# EduBOT_v2.net
KiCad netlist of a schematic drawn in Altium Designer
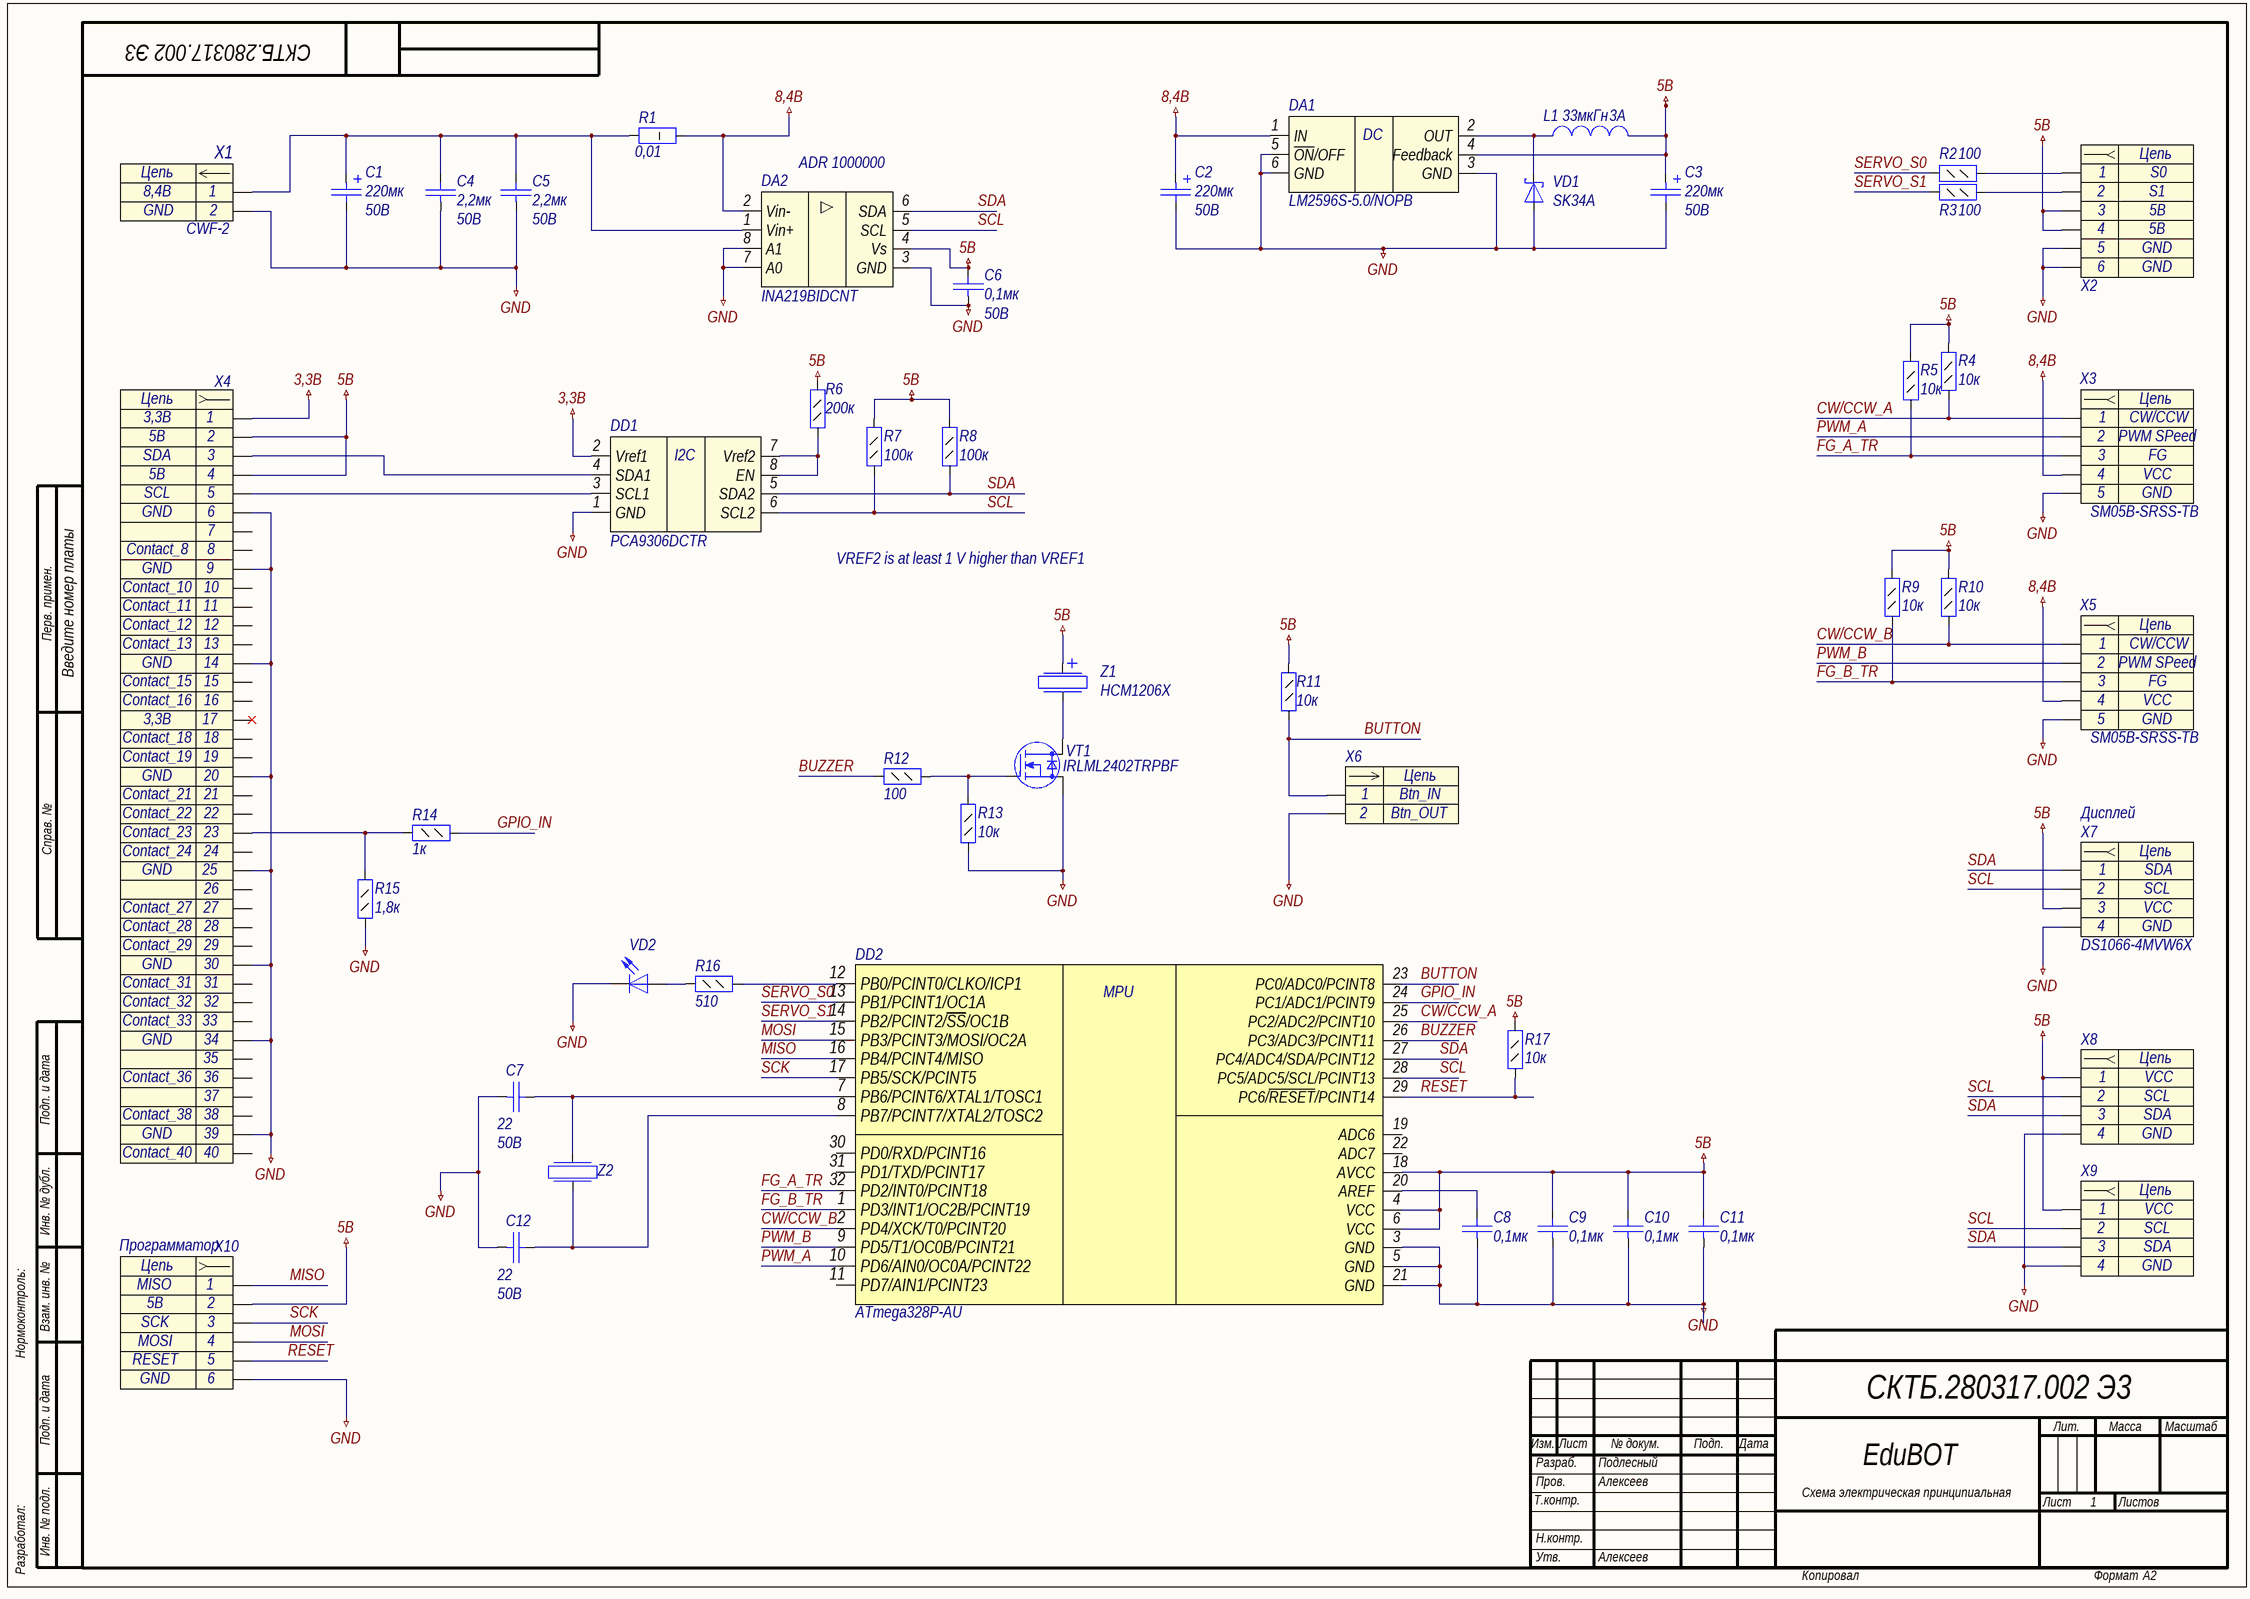
[diagram p0: EduBOT_v2.SchDoc]

(export (version "E")
  (design (tool "Eeschema 10.0.6"))
  (components
    (comp (ref "C1")
      (value "220мк")
      (footprint "Cap_SMD_radial_polar(10x10.5)")
      (description "Конденсатор полярный")
      (fields
        (field (name "VOLTAGE") "50В")
        (field (name "PART NUMBER") "ECAP SMD")
        (field (name "Comment") "Capacitor_pol")
      )
      (libsource (lib "MOP44") (part "Capacitor_pol"))
    )
    (comp (ref "C2")
      (value "220мк")
      (footprint "Cap_SMD_radial_polar(10x10.5)")
      (description "Конденсатор полярный")
      (fields
        (field (name "VOLTAGE") "50В")
        (field (name "PART NUMBER") "ECAP SMD")
        (field (name "Comment") "Capacitor_pol")
      )
      (libsource (lib "MOP44") (part "Capacitor_pol"))
    )
    (comp (ref "C3")
      (value "220мк")
      (footprint "Cap_SMD_radial_polar(10x10.5)")
      (description "Конденсатор полярный")
      (fields
        (field (name "VOLTAGE") "50В")
        (field (name "PART NUMBER") "ECAP SMD")
        (field (name "Comment") "Capacitor_pol")
      )
      (libsource (lib "MOP44") (part "Capacitor_pol"))
    )
    (comp (ref "C4")
      (value "2,2мк")
      (footprint "C1206")
      (description "Конденсатор")
      (fields
        (field (name "VOLTAGE") "50В")
        (field (name "PART NUMBER") "GRM31CR71H225KA88**L")
        (field (name "Comment") "Capacitor")
      )
      (libsource (lib "MOP44") (part "Capacitor"))
    )
    (comp (ref "C5")
      (value "2,2мк")
      (footprint "C1206")
      (description "Конденсатор")
      (fields
        (field (name "VOLTAGE") "50В")
        (field (name "PART NUMBER") "GRM31CR71H225KA88**L")
        (field (name "Comment") "Capacitor")
      )
      (libsource (lib "MOP44") (part "Capacitor"))
    )
    (comp (ref "C6")
      (value "0,1мк")
      (footprint "C0805")
      (description "Конденсатор")
      (fields
        (field (name "VOLTAGE") "50В")
        (field (name "PART NUMBER") "GRM21BR71H104KA01L ")
        (field (name "Comment") "Capacitor")
      )
      (libsource (lib "MOP44") (part "Capacitor"))
    )
    (comp (ref "C7")
      (value "22")
      (footprint "C0805")
      (description "Конденсатор")
      (fields
        (field (name "VOLTAGE") "50В")
        (field (name "PART NUMBER") "GRM21A5C2E220JW01D")
        (field (name "Comment") "Capacitor")
      )
      (libsource (lib "MOP44") (part "Capacitor"))
    )
    (comp (ref "C8")
      (value "0,1мк")
      (footprint "C0805")
      (description "Конденсатор")
      (fields (field (name "PART NUMBER") "GRM21BR71H104KA01L ") (field (name "Comment") "Capacitor"))
      (libsource (lib "MOP44") (part "Capacitor"))
    )
    (comp (ref "C9")
      (value "0,1мк")
      (footprint "C0805")
      (description "Конденсатор")
      (fields (field (name "PART NUMBER") "GRM21BR71H104KA01L ") (field (name "Comment") "Capacitor"))
      (libsource (lib "MOP44") (part "Capacitor"))
    )
    (comp (ref "C10")
      (value "0,1мк")
      (footprint "C0805")
      (description "Конденсатор")
      (fields (field (name "PART NUMBER") "GRM21BR71H104KA01L ") (field (name "Comment") "Capacitor"))
      (libsource (lib "MOP44") (part "Capacitor"))
    )
    (comp (ref "C11")
      (value "0,1мк")
      (footprint "C0805")
      (description "Конденсатор")
      (fields (field (name "PART NUMBER") "GRM21BR71H104KA01L ") (field (name "Comment") "Capacitor"))
      (libsource (lib "MOP44") (part "Capacitor"))
    )
    (comp (ref "C12")
      (value "22")
      (footprint "C0805")
      (description "Конденсатор")
      (fields
        (field (name "VOLTAGE") "50В")
        (field (name "PART NUMBER") "GRM21A5C2E220JW01D")
        (field (name "Comment") "Capacitor")
      )
      (libsource (lib "MOP44") (part "Capacitor"))
    )
    (comp (ref "DA1")
      (value "LM2596S")
      (footprint "TO-263-5")
      (description "3-A Step-Down Voltage Regulator")
      (fields
        (field (name "PART NUMBER") "LM2596S-5.0/NOPB")
        (field (name "MANUFACTURER") "Texas Instruments")
      )
      (libsource (lib "MOP44") (part "LM2596S"))
    )
    (comp (ref "DA2")
      (value "INA219BIDCNT")
      (footprint "SOT23-8")
      (description "Токочувствительный усилитель")
      (libsource (lib "MOP44") (part "INA219BIDCNT"))
    )
    (comp (ref "DD1")
      (value "PCA9306DCTR")
      (footprint "SSOP8")
      (description "DUAL BIDIRECTIONAL I2C BUS AND SMBus VOLTAGE-LEVEL TRANSLATOR")
      (libsource (lib "MOP44") (part "PCA9306DCTR"))
    )
    (comp (ref "DD2")
      (value "ATmega328P-AU")
      (footprint "TQFP-32")
      (description "Микроконтроллер 8-Бит, picoPower, AVR, 20МГц, 32КБ Flash")
      (fields (field (name "PART NUMBER") "ATmega328P-AU"))
      (libsource (lib "MOP44") (part "ATmega328P-AU"))
    )
    (comp (ref "L1")
      (value "33мкГн")
      (footprint "IND_12.8x12.8")
      (description "EMI Suppression Filter")
      (fields
        (field (name "RATED CURRENT") "3A")
        (field (name "PART NUMBER") "B82477G4333M000")
        (field (name "Comment") "Inductor")
      )
      (libsource (lib "MOP44") (part "Inductor"))
    )
    (comp (ref "R1")
      (value "0,01")
      (footprint "R2512")
      (description "Резистор")
      (fields (field (name "PART NUMBER") "RL2512FK-070R01L") (field (name "POWER") "1Вт"))
      (libsource (lib "MOP44") (part "Resistor_1Вт"))
    )
    (comp (ref "R2")
      (value "100")
      (footprint "R0805")
      (description "Резистор")
      (fields (field (name "PART NUMBER") "RC0805FR-07100RL") (field (name "POWER") "0,125Вт"))
      (libsource (lib "") (part "Resistor_0,125Вт_3"))
    )
    (comp (ref "R3")
      (value "100")
      (footprint "R0805")
      (description "Резистор")
      (fields (field (name "PART NUMBER") "RC0805FR-07100RL") (field (name "POWER") "0,125Вт"))
      (libsource (lib "") (part "Resistor_0,125Вт_3"))
    )
    (comp (ref "R4")
      (value "10к")
      (footprint "R0805")
      (description "Резистор")
      (fields (field (name "PART NUMBER") "RC0805FR-0710KL") (field (name "POWER") "0,125Вт"))
      (libsource (lib "MOP44") (part "Resistor_0,125Вт"))
    )
    (comp (ref "R5")
      (value "10к")
      (footprint "R0805")
      (description "Резистор")
      (fields (field (name "PART NUMBER") "RC0805FR-0710KL") (field (name "POWER") "0,125Вт"))
      (libsource (lib "MOP44") (part "Resistor_0,125Вт"))
    )
    (comp (ref "R6")
      (value "200к")
      (footprint "R0805")
      (description "Резистор")
      (fields (field (name "PART NUMBER") "RC0805FR-07200KL") (field (name "POWER") "0,125Вт"))
      (libsource (lib "MOP44") (part "Resistor_0,125Вт"))
    )
    (comp (ref "R7")
      (value "100к")
      (footprint "R0805")
      (description "Резистор")
      (fields (field (name "PART NUMBER") "RC0805FR-07100KL") (field (name "POWER") "0,125Вт"))
      (libsource (lib "MOP44") (part "Resistor_0,125Вт"))
    )
    (comp (ref "R8")
      (value "100к")
      (footprint "R0805")
      (description "Резистор")
      (fields (field (name "PART NUMBER") "RC0805FR-07100KL") (field (name "POWER") "0,125Вт"))
      (libsource (lib "MOP44") (part "Resistor_0,125Вт"))
    )
    (comp (ref "R9")
      (value "10к")
      (footprint "R0805")
      (description "Резистор")
      (fields (field (name "PART NUMBER") "RC0805FR-0710KL") (field (name "POWER") "0,125Вт"))
      (libsource (lib "MOP44") (part "Resistor_0,125Вт"))
    )
    (comp (ref "R10")
      (value "10к")
      (footprint "R0805")
      (description "Резистор")
      (fields (field (name "PART NUMBER") "RC0805FR-0710KL") (field (name "POWER") "0,125Вт"))
      (libsource (lib "MOP44") (part "Resistor_0,125Вт"))
    )
    (comp (ref "R11")
      (value "10к")
      (footprint "R0805")
      (description "Резистор")
      (fields (field (name "POWER") "0,125Вт") (field (name "Comment") "Resistor_0,125Вт"))
      (libsource (lib "") (part "Resistor_0,125Вт_2"))
    )
    (comp (ref "R12")
      (value "100")
      (footprint "R0805")
      (description "Резистор")
      (fields (field (name "PART NUMBER") "RC0805FR-07100RL") (field (name "POWER") "0,125Вт"))
      (libsource (lib "") (part "Resistor_0,125Вт_3"))
    )
    (comp (ref "R13")
      (value "10к")
      (footprint "R0805")
      (description "Резистор")
      (fields (field (name "PART NUMBER") "RC0805FR-0710KL") (field (name "POWER") "0,125Вт"))
      (libsource (lib "MOP44") (part "Resistor_0,125Вт"))
    )
    (comp (ref "R14")
      (value "1к")
      (footprint "R0805")
      (description "Резистор")
      (fields (field (name "PART NUMBER") "RC0805FR-071KL") (field (name "POWER") "0,125Вт"))
      (libsource (lib "") (part "Resistor_0,125Вт_1"))
    )
    (comp (ref "R15")
      (value "1,8к")
      (footprint "R0805")
      (description "Резистор")
      (fields (field (name "PART NUMBER") "RC0805FR-071K8") (field (name "POWER") "0,125Вт"))
      (libsource (lib "MOP44") (part "Resistor_0,125Вт"))
    )
    (comp (ref "R16")
      (value "510")
      (footprint "R0805")
      (description "Резистор")
      (fields (field (name "PART NUMBER") "RC0805FR-07510RL") (field (name "POWER") "0,125Вт"))
      (libsource (lib "") (part "Resistor_0,125Вт_3"))
    )
    (comp (ref "R17")
      (value "10к")
      (footprint "R0805")
      (description "Резистор")
      (fields (field (name "PART NUMBER") "RC0805FR-0710KL") (field (name "POWER") "0,125Вт"))
      (libsource (lib "MOP44") (part "Resistor_0,125Вт"))
    )
    (comp (ref "VD1")
      (value "DiodeSchottky")
      (footprint "SMA")
      (description "Диод Шоттки")
      (fields (field (name "PART NUMBER") "SK34A"))
      (libsource (lib "MOP44") (part "DiodeSchottky"))
    )
    (comp (ref "VD2")
      (value "LED")
      (footprint "L_0805")
      (description "Светодиод")
      (fields (field (name "PART NUMBER") "KP-2012EC"))
      (libsource (lib "MOP44") (part "LED"))
    )
    (comp (ref "VT1")
      (value "N-MOSFET")
      (footprint "SOT23-3")
      (fields
        (field (name "PART NUMBER") "IRLML2402TRPBF")
        (field (name "MANUFACTURER") "International Rectifier")
      )
      (libsource (lib "MOP44") (part "N-MOSFET"))
    )
    (comp (ref "X1")
      (value "~")
      (footprint "CWF-2")
      (description "Разъем - 2 конт. вилка")
      (fields (field (name "PART NAME") "CWF-2") (field (name "PART NUMBER") "DS1069-2MVW6X"))
      (libsource (lib "MOP44") (part "Header_2_plg"))
    )
    (comp (ref "X2")
      (value "Header_6_sct")
      (footprint "PLS2-6")
      (description "Разъем - 6 конт. розетка")
      (libsource (lib "MOP44") (part "Header_6_sct"))
    )
    (comp (ref "X3")
      (value "Двигатель А")
      (footprint "SM05B-SRSS-TB")
      (description "Разъем - 5 конт. розетка")
      (fields (field (name "PART NUMBER") "SM05B-SRSS-TB"))
      (libsource (lib "MOP44") (part "Header_5_sct"))
    )
    (comp (ref "X4")
      (value "~")
      (footprint "ZabugorLib:PBS-40")
      (description "Разъем - 5 конт. розетка")
      (libsource (lib "ZabugorLib") (part "Header_40"))
    )
    (comp (ref "X5")
      (value "Двигатель А")
      (footprint "SM05B-SRSS-TB")
      (description "Разъем - 5 конт. розетка")
      (fields (field (name "PART NUMBER") "SM05B-SRSS-TB"))
      (libsource (lib "MOP44") (part "Header_5_sct"))
    )
    (comp (ref "X6")
      (value "~")
      (footprint "JUMPER_2.54")
      (description "Разъем - 2 конт. вилка")
      (libsource (lib "") (part "Header_2_plg_1"))
    )
    (comp (ref "X7")
      (value "Дисплей")
      (footprint "MW-4M")
      (description "Разъем - 4 конт. розетка")
      (fields (field (name "PART NUMBER") "DS1066-4MVW6X"))
      (libsource (lib "MOP44") (part "Header_4_sct"))
    )
    (comp (ref "X8")
      (value "Header_4_sct")
      (footprint "RJ9_4P4C")
      (description "Разъем - 4 конт. розетка")
      (libsource (lib "MOP44") (part "Header_4_sct"))
    )
    (comp (ref "X9")
      (value "Header_4_sct")
      (footprint "RJ9_4P4C")
      (description "Разъем - 4 конт. розетка")
      (libsource (lib "MOP44") (part "Header_4_sct"))
    )
    (comp (ref "X10")
      (value "Программатор")
      (footprint "PLS2-6")
      (description "Разъем - 6 конт. розетка")
      (libsource (lib "") (part "Header_6_sct_1"))
    )
    (comp (ref "Z1")
      (value "~")
      (footprint "Buzzer_gen_12mm")
      (description "Пьезоизлучатель звуковой без генератора")
      (fields (field (name "PART NUMBER") "HCM1206X"))
      (libsource (lib "MOP44") (part "Buzzer"))
    )
    (comp (ref "Z2")
      (value "Crystal")
      (footprint "HC-49S")
      (description "Кварцевый резонатор")
      (fields (field (name "PART NUMBER") "16.000MHzHC-49US"))
      (libsource (lib "MOP44") (part "Crystal"))
    )
  )
  (nets
    (net (code "1") (name "/BUTTON") (class "Default")
      (node (ref "DD2") (pin "23") (pinfunction "PC0/ADC0/PCINT8_23") (pintype "passive"))
      (node (ref "R11") (pin "2") (pinfunction "2_2") (pintype "passive"))
      (node (ref "X6") (pin "1") (pinfunction "1_1") (pintype "passive"))
    )
    (net (code "2") (name "/BUZZER") (class "Default")
      (node (ref "DD2") (pin "26") (pinfunction "PC3/ADC3/PCINT11_26") (pintype "passive"))
      (node (ref "R12") (pin "1") (pinfunction "1_1") (pintype "passive"))
    )
    (net (code "3") (name "/CW{slash}CCW_A") (class "Default")
      (node (ref "DD2") (pin "25") (pinfunction "PC2/ADC2/PCINT10_25") (pintype "passive"))
      (node (ref "R4") (pin "1") (pinfunction "1_1") (pintype "passive"))
      (node (ref "X3") (pin "1") (pinfunction "1_1") (pintype "passive"))
    )
    (net (code "4") (name "/CW{slash}CCW_B") (class "Default")
      (node (ref "DD2") (pin "2") (pinfunction "PD4/XCK/T0/PCINT20_2") (pintype "passive"))
      (node (ref "R10") (pin "1") (pinfunction "1_1") (pintype "passive"))
      (node (ref "X5") (pin "1") (pinfunction "1_1") (pintype "passive"))
    )
    (net (code "5") (name "/FG_A_TR") (class "Default")
      (node (ref "DD2") (pin "32") (pinfunction "PD2/INT0/PCINT18_32") (pintype "passive"))
      (node (ref "R5") (pin "1") (pinfunction "1_1") (pintype "passive"))
      (node (ref "X3") (pin "3") (pinfunction "3_3") (pintype "passive"))
    )
    (net (code "6") (name "/FG_B_TR") (class "Default")
      (node (ref "DD2") (pin "1") (pinfunction "PD3/INT1/OC2B/PCINT19_1") (pintype "passive"))
      (node (ref "R9") (pin "1") (pinfunction "1_1") (pintype "passive"))
      (node (ref "X5") (pin "3") (pinfunction "3_3") (pintype "passive"))
    )
    (net (code "7") (name "/GPIO_IN") (class "Default")
      (node (ref "DD2") (pin "24") (pinfunction "PC1/ADC1/PCINT9_24") (pintype "passive"))
      (node (ref "R14") (pin "1") (pinfunction "1_1") (pintype "passive"))
    )
    (net (code "8") (name "/MISO") (class "Default")
      (node (ref "DD2") (pin "16") (pinfunction "PB4/PCINT4/MISO_16") (pintype "passive"))
      (node (ref "X10") (pin "1") (pinfunction "1_1") (pintype "passive"))
    )
    (net (code "9") (name "/MOSI") (class "Default")
      (node (ref "DD2") (pin "15") (pinfunction "PB3/PCINT3/MOSI/OC2A_15") (pintype "passive"))
      (node (ref "X10") (pin "4") (pinfunction "4_4") (pintype "passive"))
    )
    (net (code "10") (name "/PWM_A") (class "Default")
      (node (ref "DD2") (pin "10") (pinfunction "PD6/AIN0/OC0A/PCINT22_10") (pintype "passive"))
      (node (ref "X3") (pin "2") (pinfunction "2_2") (pintype "passive"))
    )
    (net (code "11") (name "/PWM_B") (class "Default")
      (node (ref "DD2") (pin "9") (pinfunction "PD5/T1/OC0B/PCINT21_9") (pintype "passive"))
      (node (ref "X5") (pin "2") (pinfunction "2_2") (pintype "passive"))
    )
    (net (code "12") (name "/RESET") (class "Default")
      (node (ref "DD2") (pin "29") (pinfunction "PC6/~{RESET}/PCINT14_29") (pintype "passive"))
      (node (ref "R17") (pin "1") (pinfunction "1_1") (pintype "passive"))
      (node (ref "X10") (pin "5") (pinfunction "5_5") (pintype "passive"))
    )
    (net (code "13") (name "/SCK") (class "Default")
      (node (ref "DD2") (pin "17") (pinfunction "PB5/SCK/PCINT5_17") (pintype "passive"))
      (node (ref "X10") (pin "3") (pinfunction "3_3") (pintype "passive"))
    )
    (net (code "14") (name "/SCL") (class "Default")
      (node (ref "DA2") (pin "5") (pinfunction "SCL_5") (pintype "passive"))
      (node (ref "DD1") (pin "6") (pinfunction "SCL2_6") (pintype "power_in"))
      (node (ref "DD2") (pin "28") (pinfunction "PC5/ADC5/SCL/PCINT13_28") (pintype "passive"))
      (node (ref "R7") (pin "1") (pinfunction "1_1") (pintype "passive"))
      (node (ref "X7") (pin "2") (pinfunction "2_2") (pintype "passive"))
      (node (ref "X8") (pin "2") (pinfunction "2_2") (pintype "passive"))
      (node (ref "X9") (pin "2") (pinfunction "2_2") (pintype "passive"))
    )
    (net (code "15") (name "/SDA") (class "Default")
      (node (ref "DA2") (pin "6") (pinfunction "SDA_6") (pintype "passive"))
      (node (ref "DD1") (pin "5") (pinfunction "SDA2_5") (pintype "power_in"))
      (node (ref "DD2") (pin "27") (pinfunction "PC4/ADC4/SDA/PCINT12_27") (pintype "passive"))
      (node (ref "R8") (pin "1") (pinfunction "1_1") (pintype "passive"))
      (node (ref "X7") (pin "1") (pinfunction "1_1") (pintype "passive"))
      (node (ref "X8") (pin "3") (pinfunction "3_3") (pintype "passive"))
      (node (ref "X9") (pin "3") (pinfunction "3_3") (pintype "passive"))
    )
    (net (code "16") (name "/SERVO_S0") (class "Default")
      (node (ref "DD2") (pin "13") (pinfunction "PB1/PCINT1/OC1A_13") (pintype "passive"))
      (node (ref "R2") (pin "1") (pinfunction "1_1") (pintype "passive"))
    )
    (net (code "17") (name "/SERVO_S1") (class "Default")
      (node (ref "DD2") (pin "14") (pinfunction "PB2/PCINT2/~{SS}/OC1B_14") (pintype "passive"))
      (node (ref "R3") (pin "1") (pinfunction "1_1") (pintype "passive"))
    )
    (net (code "18") (name "3,3B") (class "Default")
      (node (ref "DD1") (pin "2") (pinfunction "Vref1_2") (pintype "power_in"))
      (node (ref "X4") (pin "1") (pinfunction "1_1") (pintype "passive"))
    )
    (net (code "19") (name "5В") (class "Default")
      (node (ref "C10") (pin "2") (pinfunction "2_2") (pintype "passive"))
      (node (ref "C11") (pin "2") (pinfunction "2_2") (pintype "passive"))
      (node (ref "C3") (pin "1") (pinfunction "1_1") (pintype "passive"))
      (node (ref "C6") (pin "2") (pinfunction "2_2") (pintype "passive"))
      (node (ref "C9") (pin "2") (pinfunction "2_2") (pintype "passive"))
      (node (ref "DA1") (pin "4") (pinfunction "Feedback_4") (pintype "power_in"))
      (node (ref "DA2") (pin "4") (pinfunction "Vs_4") (pintype "passive"))
      (node (ref "DD2") (pin "18") (pinfunction "AVCC_18") (pintype "passive"))
      (node (ref "DD2") (pin "4") (pinfunction "VCC_4") (pintype "passive"))
      (node (ref "DD2") (pin "6") (pinfunction "VCC_6") (pintype "passive"))
      (node (ref "L1") (pin "2") (pinfunction "2_2") (pintype "passive"))
      (node (ref "R10") (pin "2") (pinfunction "2_2") (pintype "passive"))
      (node (ref "R11") (pin "1") (pinfunction "1_1") (pintype "passive"))
      (node (ref "R17") (pin "2") (pinfunction "2_2") (pintype "passive"))
      (node (ref "R4") (pin "2") (pinfunction "2_2") (pintype "passive"))
      (node (ref "R5") (pin "2") (pinfunction "2_2") (pintype "passive"))
      (node (ref "R6") (pin "2") (pinfunction "2_2") (pintype "passive"))
      (node (ref "R7") (pin "2") (pinfunction "2_2") (pintype "passive"))
      (node (ref "R8") (pin "2") (pinfunction "2_2") (pintype "passive"))
      (node (ref "R9") (pin "2") (pinfunction "2_2") (pintype "passive"))
      (node (ref "X10") (pin "2") (pinfunction "2_2") (pintype "passive"))
      (node (ref "X2") (pin "3") (pinfunction "3_3") (pintype "passive"))
      (node (ref "X2") (pin "4") (pinfunction "4_4") (pintype "passive"))
      (node (ref "X4") (pin "2") (pinfunction "2_2") (pintype "passive"))
      (node (ref "X4") (pin "4") (pinfunction "4_4") (pintype "passive"))
      (node (ref "X7") (pin "3") (pinfunction "3_3") (pintype "passive"))
      (node (ref "X8") (pin "1") (pinfunction "1_1") (pintype "passive"))
      (node (ref "X9") (pin "1") (pinfunction "1_1") (pintype "passive"))
      (node (ref "Z1") (pin "1") (pinfunction "1_1") (pintype "passive"))
    )
    (net (code "20") (name "8,4В") (class "Default")
      (node (ref "C2") (pin "1") (pinfunction "1_1") (pintype "passive"))
      (node (ref "DA1") (pin "1") (pinfunction "IN_1") (pintype "power_in"))
      (node (ref "DA2") (pin "2") (pinfunction "Vin-_2") (pintype "passive"))
      (node (ref "R1") (pin "2") (pinfunction "5_2") (pintype "passive"))
      (node (ref "X3") (pin "4") (pinfunction "4_4") (pintype "passive"))
      (node (ref "X5") (pin "4") (pinfunction "4_4") (pintype "passive"))
    )
    (net (code "21") (name "GND") (class "Default")
      (node (ref "C1") (pin "2") (pinfunction "2_2") (pintype "passive"))
      (node (ref "C10") (pin "1") (pinfunction "1_1") (pintype "passive"))
      (node (ref "C11") (pin "1") (pinfunction "1_1") (pintype "passive"))
      (node (ref "C12") (pin "1") (pinfunction "1_1") (pintype "passive"))
      (node (ref "C2") (pin "2") (pinfunction "2_2") (pintype "passive"))
      (node (ref "C3") (pin "2") (pinfunction "2_2") (pintype "passive"))
      (node (ref "C4") (pin "1") (pinfunction "1_1") (pintype "passive"))
      (node (ref "C5") (pin "1") (pinfunction "1_1") (pintype "passive"))
      (node (ref "C6") (pin "1") (pinfunction "1_1") (pintype "passive"))
      (node (ref "C7") (pin "1") (pinfunction "1_1") (pintype "passive"))
      (node (ref "C8") (pin "1") (pinfunction "1_1") (pintype "passive"))
      (node (ref "C9") (pin "1") (pinfunction "1_1") (pintype "passive"))
      (node (ref "DA1") (pin "3") (pinfunction "GND_3") (pintype "power_in"))
      (node (ref "DA1") (pin "5") (pinfunction "~{ON}/OFF_5") (pintype "power_in"))
      (node (ref "DA1") (pin "6") (pinfunction "GND_6") (pintype "power_in"))
      (node (ref "DA2") (pin "3") (pinfunction "GND_3") (pintype "passive"))
      (node (ref "DA2") (pin "7") (pinfunction "A0_7") (pintype "passive"))
      (node (ref "DA2") (pin "8") (pinfunction "A1_8") (pintype "passive"))
      (node (ref "DD1") (pin "1") (pinfunction "GND_1") (pintype "power_in"))
      (node (ref "DD2") (pin "21") (pinfunction "GND_21") (pintype "passive"))
      (node (ref "DD2") (pin "3") (pinfunction "GND_3") (pintype "passive"))
      (node (ref "DD2") (pin "5") (pinfunction "GND_5") (pintype "passive"))
      (node (ref "R13") (pin "1") (pinfunction "1_1") (pintype "passive"))
      (node (ref "R15") (pin "1") (pinfunction "1_1") (pintype "passive"))
      (node (ref "VD1") (pin "2") (pinfunction "A_2") (pintype "passive"))
      (node (ref "VD2") (pin "1") (pinfunction "K_1") (pintype "passive"))
      (node (ref "VT1") (pin "3") (pinfunction "S_3") (pintype "passive"))
      (node (ref "X1") (pin "2") (pinfunction "2_2") (pintype "passive"))
      (node (ref "X10") (pin "6") (pinfunction "6_6") (pintype "passive"))
      (node (ref "X2") (pin "5") (pinfunction "5_5") (pintype "passive"))
      (node (ref "X2") (pin "6") (pinfunction "6_6") (pintype "passive"))
      (node (ref "X3") (pin "5") (pinfunction "5_5") (pintype "passive"))
      (node (ref "X4") (pin "14") (pinfunction "14_14") (pintype "passive"))
      (node (ref "X4") (pin "20") (pinfunction "20_20") (pintype "passive"))
      (node (ref "X4") (pin "25") (pinfunction "25_25") (pintype "passive"))
      (node (ref "X4") (pin "30") (pinfunction "30_30") (pintype "passive"))
      (node (ref "X4") (pin "34") (pinfunction "34_34") (pintype "passive"))
      (node (ref "X4") (pin "39") (pinfunction "39_39") (pintype "passive"))
      (node (ref "X4") (pin "6") (pinfunction "6_6") (pintype "passive"))
      (node (ref "X4") (pin "9") (pinfunction "9_9") (pintype "passive"))
      (node (ref "X5") (pin "5") (pinfunction "5_5") (pintype "passive"))
      (node (ref "X6") (pin "2") (pinfunction "2_2") (pintype "passive"))
      (node (ref "X7") (pin "4") (pinfunction "4_4") (pintype "passive"))
      (node (ref "X8") (pin "4") (pinfunction "4_4") (pintype "passive"))
      (node (ref "X9") (pin "4") (pinfunction "4_4") (pintype "passive"))
    )
    (net (code "22") (name "Net-(DA1-OUT)") (class "Default")
      (node (ref "DA1") (pin "2") (pinfunction "OUT_2") (pintype "power_in"))
      (node (ref "L1") (pin "1") (pinfunction "1_1") (pintype "passive"))
      (node (ref "VD1") (pin "1") (pinfunction "K_1") (pintype "passive"))
    )
    (net (code "23") (name "Net-(DA2-Vin+)") (class "Default")
      (node (ref "C1") (pin "1") (pinfunction "1_1") (pintype "passive"))
      (node (ref "C4") (pin "2") (pinfunction "2_2") (pintype "passive"))
      (node (ref "C5") (pin "2") (pinfunction "2_2") (pintype "passive"))
      (node (ref "DA2") (pin "1") (pinfunction "Vin+_1") (pintype "passive"))
      (node (ref "R1") (pin "1") (pinfunction "1_1") (pintype "passive"))
      (node (ref "X1") (pin "1") (pinfunction "1_1") (pintype "passive"))
    )
    (net (code "24") (name "Net-(DD1-EN)") (class "Default")
      (node (ref "DD1") (pin "7") (pinfunction "Vref2_7") (pintype "power_in"))
      (node (ref "DD1") (pin "8") (pinfunction "EN_8") (pintype "power_in"))
      (node (ref "R6") (pin "1") (pinfunction "1_1") (pintype "passive"))
    )
    (net (code "25") (name "Net-(DD1-SCL1)") (class "Default")
      (node (ref "DD1") (pin "3") (pinfunction "SCL1_3") (pintype "power_in"))
      (node (ref "X4") (pin "5") (pinfunction "5_5") (pintype "passive"))
    )
    (net (code "26") (name "Net-(DD1-SDA1)") (class "Default")
      (node (ref "DD1") (pin "4") (pinfunction "SDA1_4") (pintype "power_in"))
      (node (ref "X4") (pin "3") (pinfunction "3_3") (pintype "passive"))
    )
    (net (code "27") (name "Net-(DD2-AREF)") (class "Default")
      (node (ref "C8") (pin "2") (pinfunction "2_2") (pintype "passive"))
      (node (ref "DD2") (pin "20") (pinfunction "AREF_20") (pintype "passive"))
    )
    (net (code "28") (name "Net-(DD2-PB0{slash}PCINT0{slash}CLKO{slash}ICP1)") (class "Default")
      (node (ref "DD2") (pin "12") (pinfunction "PB0/PCINT0/CLKO/ICP1_12") (pintype "passive"))
      (node (ref "R16") (pin "2") (pinfunction "2_2") (pintype "passive"))
    )
    (net (code "29") (name "Net-(DD2-PB6{slash}PCINT6{slash}XTAL1{slash}TOSC1)") (class "Default")
      (node (ref "C7") (pin "2") (pinfunction "2_2") (pintype "passive"))
      (node (ref "DD2") (pin "7") (pinfunction "PB6/PCINT6/XTAL1/TOSC1_7") (pintype "passive"))
      (node (ref "Z2") (pin "2") (pinfunction "2_2") (pintype "passive"))
    )
    (net (code "30") (name "Net-(DD2-PB7{slash}PCINT7{slash}XTAL2{slash}TOSC2)") (class "Default")
      (node (ref "C12") (pin "2") (pinfunction "2_2") (pintype "passive"))
      (node (ref "DD2") (pin "8") (pinfunction "PB7/PCINT7/XTAL2/TOSC2_8") (pintype "passive"))
      (node (ref "Z2") (pin "1") (pinfunction "1_1") (pintype "passive"))
    )
    (net (code "31") (name "Net-(R2-Pad2)") (class "Default")
      (node (ref "R2") (pin "2") (pinfunction "2_2") (pintype "passive"))
      (node (ref "X2") (pin "1") (pinfunction "1_1") (pintype "passive"))
    )
    (net (code "32") (name "Net-(R3-Pad2)") (class "Default")
      (node (ref "R3") (pin "2") (pinfunction "2_2") (pintype "passive"))
      (node (ref "X2") (pin "2") (pinfunction "2_2") (pintype "passive"))
    )
    (net (code "33") (name "Net-(R14-Pad2)") (class "Default")
      (node (ref "R14") (pin "2") (pinfunction "2_2") (pintype "passive"))
      (node (ref "R15") (pin "2") (pinfunction "2_2") (pintype "passive"))
      (node (ref "X4") (pin "23") (pinfunction "23_23") (pintype "passive"))
    )
    (net (code "34") (name "Net-(VD2-A)") (class "Default")
      (node (ref "R16") (pin "1") (pinfunction "1_1") (pintype "passive"))
      (node (ref "VD2") (pin "2") (pinfunction "A_2") (pintype "passive"))
    )
    (net (code "35") (name "Net-(VT1-D)") (class "Default")
      (node (ref "VT1") (pin "2") (pinfunction "D_2") (pintype "passive"))
      (node (ref "Z1") (pin "2") (pinfunction "2_2") (pintype "passive"))
    )
    (net (code "36") (name "Net-(VT1-G)") (class "Default")
      (node (ref "R12") (pin "2") (pinfunction "2_2") (pintype "passive"))
      (node (ref "R13") (pin "2") (pinfunction "2_2") (pintype "passive"))
      (node (ref "VT1") (pin "1") (pinfunction "G_1") (pintype "passive"))
    )
    (net (code "37") (name "unconnected-(DD2-ADC6-Pad19)") (class "Default")
      (node (ref "DD2") (pin "19") (pinfunction "ADC6_19") (pintype "passive"))
    )
    (net (code "38") (name "unconnected-(DD2-ADC7-Pad22)") (class "Default")
      (node (ref "DD2") (pin "22") (pinfunction "ADC7_22") (pintype "passive"))
    )
    (net (code "39") (name "unconnected-(DD2-PD0{slash}RXD{slash}PCINT16-Pad30)") (class "Default")
      (node (ref "DD2") (pin "30") (pinfunction "PD0/RXD/PCINT16_30") (pintype "passive"))
    )
    (net (code "40") (name "unconnected-(DD2-PD1{slash}TXD{slash}PCINT17-Pad31)") (class "Default")
      (node (ref "DD2") (pin "31") (pinfunction "PD1/TXD/PCINT17_31") (pintype "passive"))
    )
    (net (code "41") (name "unconnected-(DD2-PD7{slash}AIN1{slash}PCINT23-Pad11)") (class "Default")
      (node (ref "DD2") (pin "11") (pinfunction "PD7/AIN1/PCINT23_11") (pintype "passive"))
    )
    (net (code "42") (name "unconnected-(X4-Pad7)") (class "Default")
      (node (ref "X4") (pin "7") (pinfunction "7_7") (pintype "passive"))
    )
    (net (code "43") (name "unconnected-(X4-Pad8)") (class "Default")
      (node (ref "X4") (pin "8") (pinfunction "8_8") (pintype "passive"))
    )
    (net (code "44") (name "unconnected-(X4-Pad10)") (class "Default")
      (node (ref "X4") (pin "10") (pinfunction "10_10") (pintype "passive"))
    )
    (net (code "45") (name "unconnected-(X4-Pad11)") (class "Default")
      (node (ref "X4") (pin "11") (pinfunction "11_11") (pintype "passive"))
    )
    (net (code "46") (name "unconnected-(X4-Pad12)") (class "Default")
      (node (ref "X4") (pin "12") (pinfunction "12_12") (pintype "passive"))
    )
    (net (code "47") (name "unconnected-(X4-Pad13)") (class "Default")
      (node (ref "X4") (pin "13") (pinfunction "13_13") (pintype "passive"))
    )
    (net (code "48") (name "unconnected-(X4-Pad15)") (class "Default")
      (node (ref "X4") (pin "15") (pinfunction "15_15") (pintype "passive"))
    )
    (net (code "49") (name "unconnected-(X4-Pad16)") (class "Default")
      (node (ref "X4") (pin "16") (pinfunction "16_16") (pintype "passive"))
    )
    (net (code "50") (name "unconnected-(X4-Pad17)") (class "Default")
      (node (ref "X4") (pin "17") (pinfunction "17_17") (pintype "passive+no_connect"))
    )
    (net (code "51") (name "unconnected-(X4-Pad18)") (class "Default")
      (node (ref "X4") (pin "18") (pinfunction "18_18") (pintype "passive"))
    )
    (net (code "52") (name "unconnected-(X4-Pad19)") (class "Default")
      (node (ref "X4") (pin "19") (pinfunction "19_19") (pintype "passive"))
    )
    (net (code "53") (name "unconnected-(X4-Pad21)") (class "Default")
      (node (ref "X4") (pin "21") (pinfunction "21_21") (pintype "passive"))
    )
    (net (code "54") (name "unconnected-(X4-Pad22)") (class "Default")
      (node (ref "X4") (pin "22") (pinfunction "22_22") (pintype "passive"))
    )
    (net (code "55") (name "unconnected-(X4-Pad24)") (class "Default")
      (node (ref "X4") (pin "24") (pinfunction "24_24") (pintype "passive"))
    )
    (net (code "56") (name "unconnected-(X4-Pad26)") (class "Default")
      (node (ref "X4") (pin "26") (pinfunction "26_26") (pintype "passive"))
    )
    (net (code "57") (name "unconnected-(X4-Pad27)") (class "Default")
      (node (ref "X4") (pin "27") (pinfunction "27_27") (pintype "passive"))
    )
    (net (code "58") (name "unconnected-(X4-Pad28)") (class "Default")
      (node (ref "X4") (pin "28") (pinfunction "28_28") (pintype "passive"))
    )
    (net (code "59") (name "unconnected-(X4-Pad29)") (class "Default")
      (node (ref "X4") (pin "29") (pinfunction "29_29") (pintype "passive"))
    )
    (net (code "60") (name "unconnected-(X4-Pad31)") (class "Default")
      (node (ref "X4") (pin "31") (pinfunction "31_31") (pintype "passive"))
    )
    (net (code "61") (name "unconnected-(X4-Pad32)") (class "Default")
      (node (ref "X4") (pin "32") (pinfunction "32_32") (pintype "passive"))
    )
    (net (code "62") (name "unconnected-(X4-Pad33)") (class "Default")
      (node (ref "X4") (pin "33") (pinfunction "33_33") (pintype "passive"))
    )
    (net (code "63") (name "unconnected-(X4-Pad35)") (class "Default")
      (node (ref "X4") (pin "35") (pinfunction "35_35") (pintype "passive"))
    )
    (net (code "64") (name "unconnected-(X4-Pad36)") (class "Default")
      (node (ref "X4") (pin "36") (pinfunction "36_36") (pintype "passive"))
    )
    (net (code "65") (name "unconnected-(X4-Pad37)") (class "Default")
      (node (ref "X4") (pin "37") (pinfunction "37_37") (pintype "passive"))
    )
    (net (code "66") (name "unconnected-(X4-Pad38)") (class "Default")
      (node (ref "X4") (pin "38") (pinfunction "38_38") (pintype "passive"))
    )
    (net (code "67") (name "unconnected-(X4-Pad40)") (class "Default")
      (node (ref "X4") (pin "40") (pinfunction "40_40") (pintype "passive"))
    )
  )
)
